# design.net
KiCad netlist of a schematic drawn in EasyEDA Pro
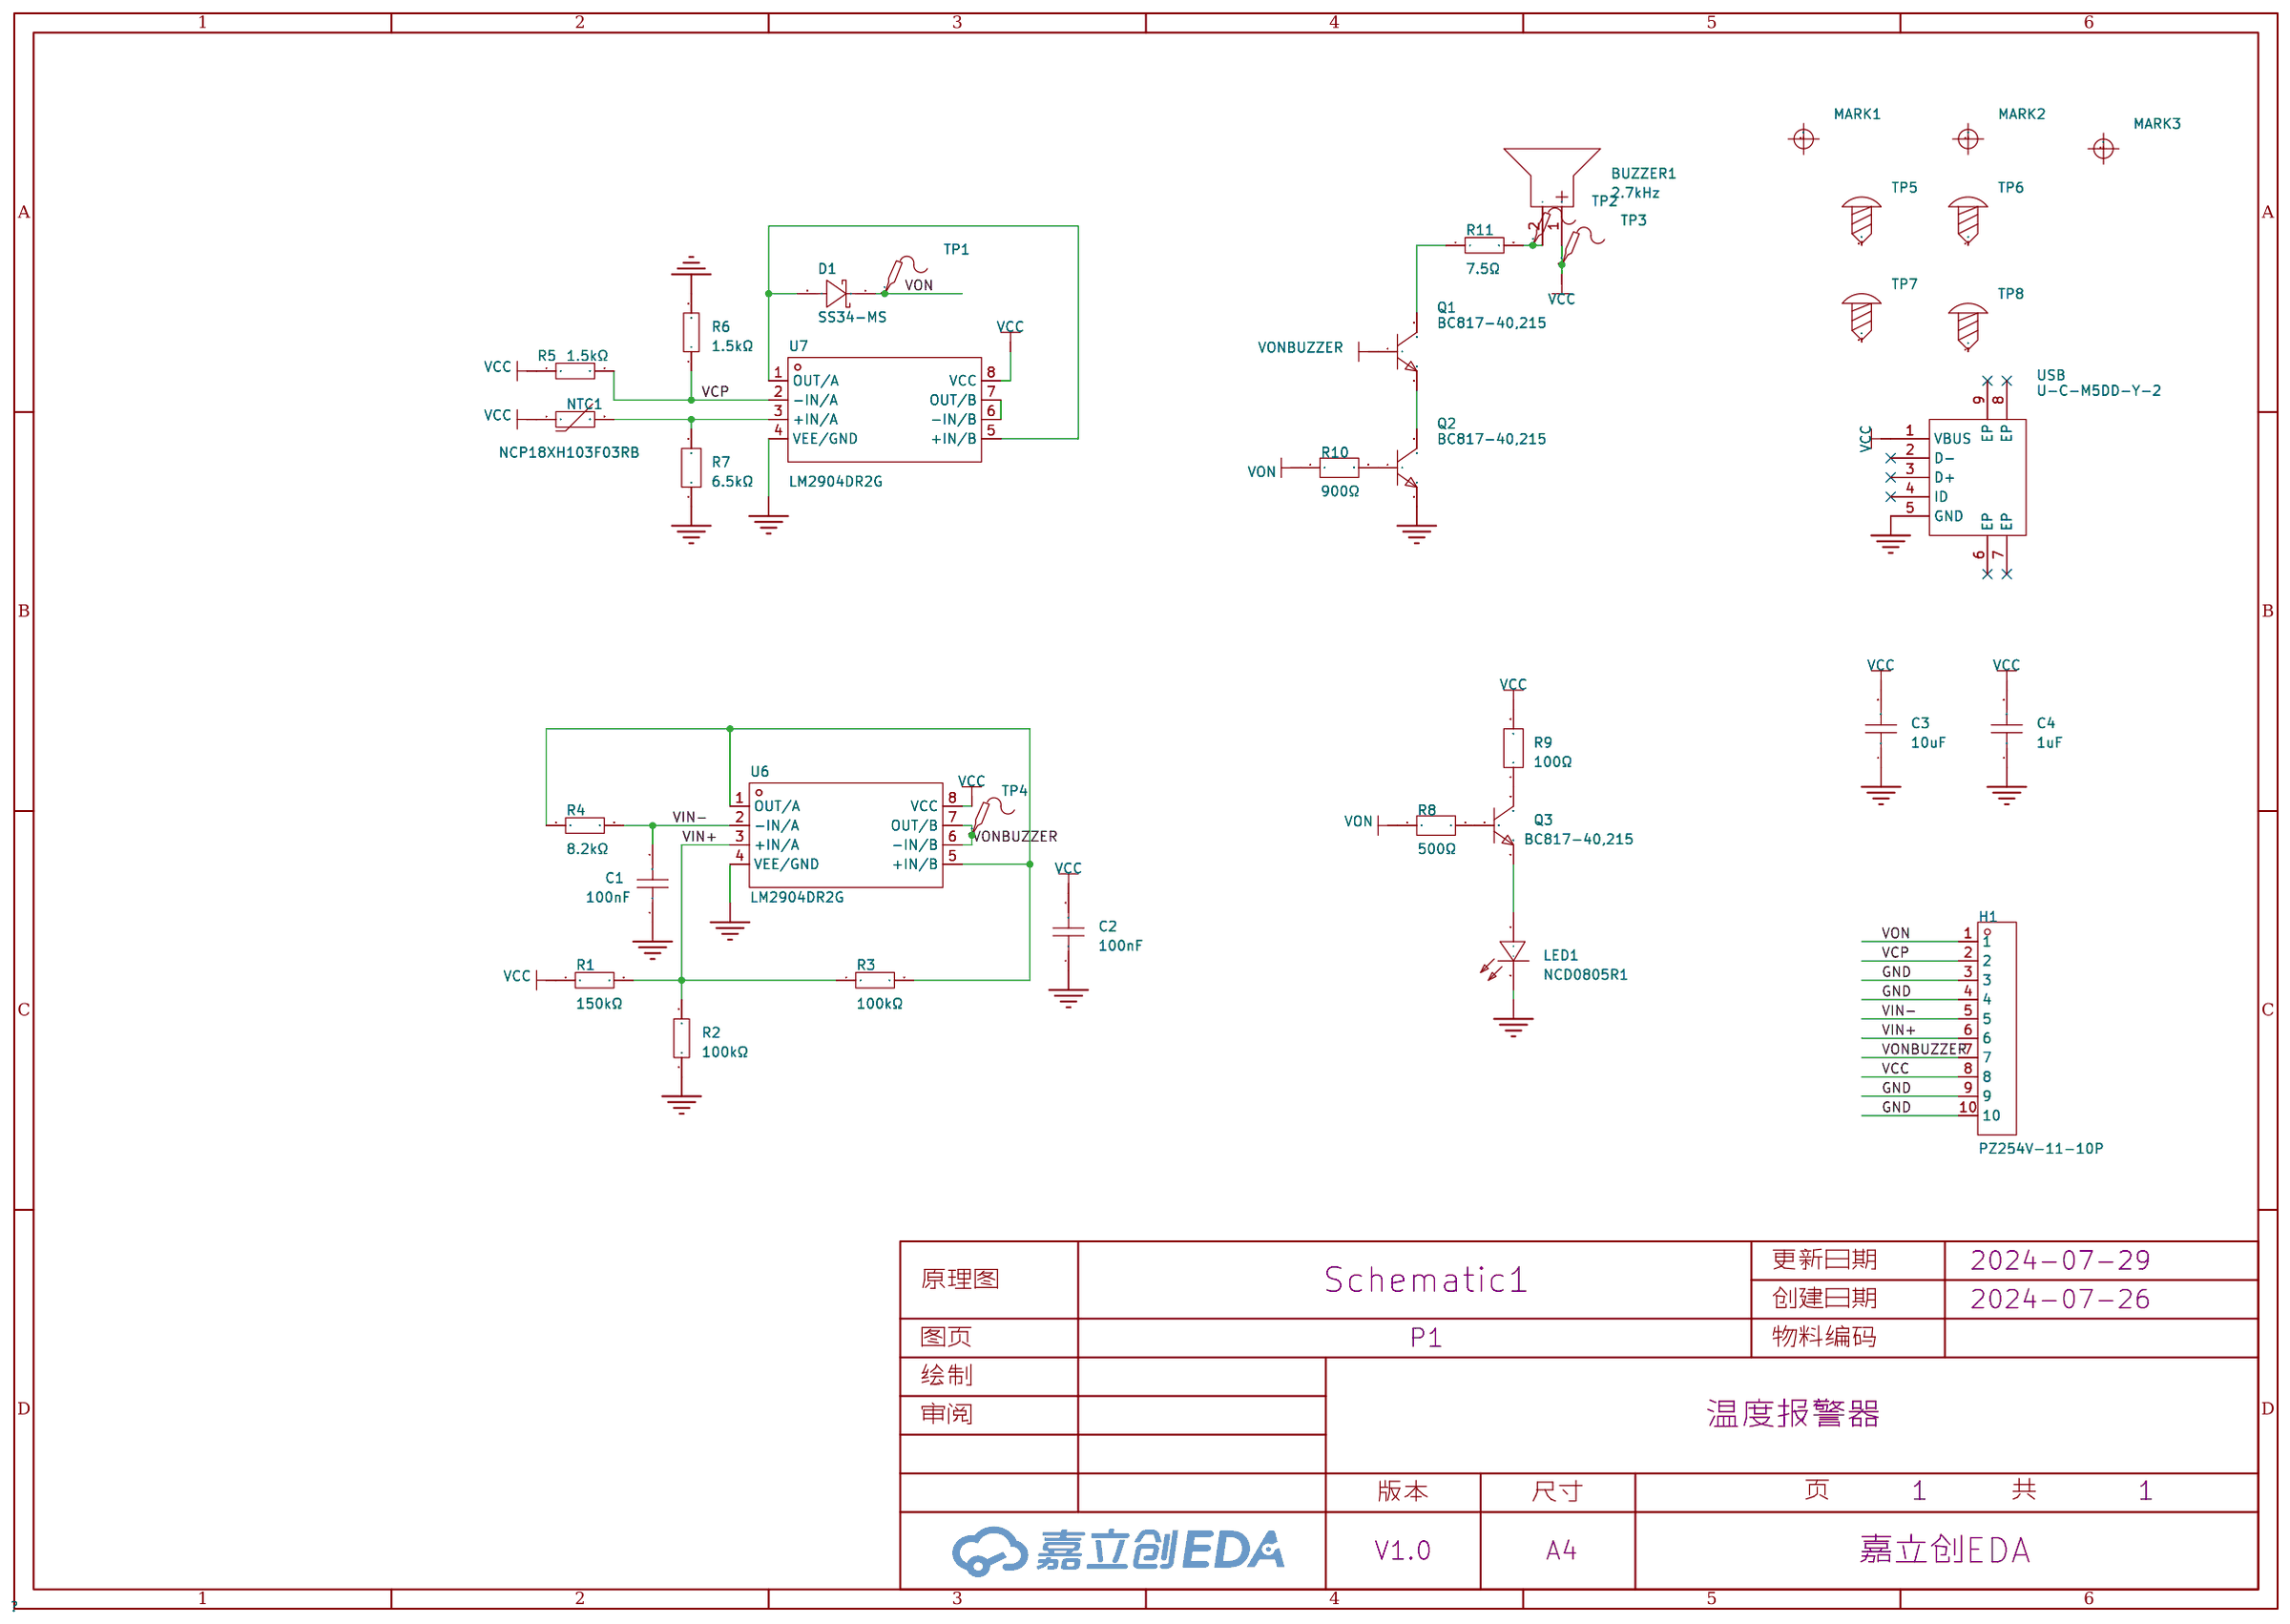
[diagram p0: schematic sheet]

(export (version "E")
  (design (tool "Eeschema 10.0.6"))
  (components
    (comp (ref "BUZZER1")
      (value "2.7kHz")
      (footprint "easyedapro:BUZ-TH_BD9.0-P4.00-D0.6-FD")
      (description "驱动方式:无源(外部驱动);构造类型:电磁式;频率:2.7kHz;声压(SPL):85dB@5V,10cm;")
      (fields
        (field (name "Manufacturer Part") "YS-MBZ9042C05R42")
        (field (name "Manufacturer") "Fengming(锋鸣电子)")
      )
      (libsource (lib "easyedapro") (part "YS-MBZ9042C05R42"))
    )
    (comp (ref "C1")
      (value "100nF")
      (footprint "easyedapro:C0603")
      (description "容值:100nF;精度:±10%;额定电压:50V;材质(温度系数):X7R;")
      (fields
        (field (name "Manufacturer Part") "CC0603KRX7R9BB104")
        (field (name "Manufacturer") "YAGEO(国巨)")
      )
      (libsource (lib "easyedapro") (part "CC0603KRX7R9BB104"))
    )
    (comp (ref "C2")
      (value "100nF")
      (footprint "easyedapro:C0603")
      (description "容值:100nF;精度:±10%;额定电压:50V;材质(温度系数):X7R;")
      (fields
        (field (name "Manufacturer Part") "CC0603KRX7R9BB104")
        (field (name "Manufacturer") "YAGEO(国巨)")
      )
      (libsource (lib "easyedapro") (part "CC0603KRX7R9BB104"))
    )
    (comp (ref "C3")
      (value "10uF")
      (footprint "easyedapro:C0603")
      (description "容值:10uF;精度:±10%;额定电压:10V;材质(温度系数):X5R;")
      (fields
        (field (name "Manufacturer Part") "CL10A106KP8NNNC")
        (field (name "Manufacturer") "SAMSUNG(三星)")
      )
      (libsource (lib "easyedapro") (part "CL10A106KP8NNNC"))
    )
    (comp (ref "C4")
      (value "1uF")
      (footprint "easyedapro:C0603")
      (description "容值:1uF;精度:±10%;额定电压:50V;材质(温度系数):X5R;")
      (fields
        (field (name "Manufacturer Part") "CL10A105KB8NNNC")
        (field (name "Manufacturer") "SAMSUNG(三星)")
      )
      (libsource (lib "easyedapro") (part "CL10A105KB8NNNC"))
    )
    (comp (ref "D1")
      (value "SS34-MS")
      (footprint "easyedapro:DO-214AC_L4.3-W2.7-LS5.0-RD")
      (description "二极管配置:-;正向压降(Vf):550mV@3A;直流反向耐压(Vr):40V;整流电流:3A;")
      (fields (field (name "Manufacturer") "MSKSEMI(美森科)"))
      (libsource (lib "easyedapro") (part "SS34-MS"))
    )
    (comp (ref "H1")
      (value "PZ254V-11-10P")
      (footprint "easyedapro:HDR-TH_10P-P2.54-V-M")
      (fields (field (name "Manufacturer") "XFCN(兴飞)"))
      (libsource (lib "easyedapro") (part "PZ254V-11-10P"))
    )
    (comp (ref "LED1")
      (value "NCD0805R1")
      (footprint "easyedapro:LED0805-R-RD")
      (fields (field (name "Manufacturer") "国星光电"))
      (libsource (lib "easyedapro") (part "FC-2012HRK-620D"))
    )
    (comp (ref "MARK1")
      (value "~")
      (footprint "easyedapro:Mark-Point-1mm")
      (description "Mark点")
      (libsource (lib "easyedapro") (part "Mark-Point"))
    )
    (comp (ref "MARK2")
      (value "~")
      (footprint "easyedapro:Mark-Point-1mm")
      (description "Mark点")
      (libsource (lib "easyedapro") (part "Mark-Point"))
    )
    (comp (ref "MARK3")
      (value "~")
      (footprint "easyedapro:Mark-Point-1mm")
      (description "Mark点")
      (libsource (lib "easyedapro") (part "Mark-Point"))
    )
    (comp (ref "NTC1")
      (value "NCP18XH103F03RB")
      (footprint "easyedapro:R0603")
      (description "阻值(25°C):10kΩ;B值(25°C/50°C):3380K;电阻精度:±1%;功率:100mW;B值精度:±1%;最大稳态电流(25°C):310uA;")
      (fields (field (name "Manufacturer") "muRata(村田)"))
      (libsource (lib "easyedapro") (part "NCP18XH103F03RB"))
    )
    (comp (ref "Q1")
      (value "BC817-40,215")
      (footprint "easyedapro:SOT-23-3_L2.9-W1.6-P1.90-LS2.8-BR")
      (description "晶体管类型:NPN;集电极电流(Ic):500mA;集射极击穿电压(Vceo):45V;功率(Pd):250mW;直流电流增益(hFE@Ic,Vce):250@100mA,1V;")
      (fields (field (name "Manufacturer") "Nexperia(安世)"))
      (libsource (lib "easyedapro") (part "BC817-40,215"))
    )
    (comp (ref "Q2")
      (value "BC817-40,215")
      (footprint "easyedapro:SOT-23-3_L2.9-W1.6-P1.90-LS2.8-BR")
      (description "晶体管类型:NPN;集电极电流(Ic):500mA;集射极击穿电压(Vceo):45V;功率(Pd):250mW;直流电流增益(hFE@Ic,Vce):250@100mA,1V;")
      (fields (field (name "Manufacturer") "Nexperia(安世)"))
      (libsource (lib "easyedapro") (part "BC817-40,215"))
    )
    (comp (ref "Q3")
      (value "BC817-40,215")
      (footprint "easyedapro:SOT-23-3_L2.9-W1.6-P1.90-LS2.8-BR")
      (description "晶体管类型:NPN;集电极电流(Ic):500mA;集射极击穿电压(Vceo):45V;功率(Pd):250mW;直流电流增益(hFE@Ic,Vce):250@100mA,1V;")
      (fields (field (name "Manufacturer") "Nexperia(安世)"))
      (libsource (lib "easyedapro") (part "BC817-40,215"))
    )
    (comp (ref "R1")
      (value "150kΩ")
      (footprint "easyedapro:R0603")
      (description "电阻类型:厚膜电阻;阻值:150kΩ;精度:±1%;功率:100mW;最大工作电压:75V;温度系数:±100ppm/°C;")
      (fields
        (field (name "Manufacturer Part") "0603WAF1503T5E")
        (field (name "Manufacturer") "UNI-ROYAL(厚声)")
      )
      (libsource (lib "easyedapro") (part "0603WAF1503T5E"))
    )
    (comp (ref "R2")
      (value "100kΩ")
      (footprint "easyedapro:R0603")
      (description "电阻类型:厚膜电阻;阻值:100kΩ;精度:±1%;功率:100mW;最大工作电压:75V;温度系数:±100ppm/°C;")
      (fields
        (field (name "Manufacturer Part") "0603WAF1003T5E")
        (field (name "Manufacturer") "UNI-ROYAL(厚声)")
      )
      (libsource (lib "easyedapro") (part "0603WAF1003T5E"))
    )
    (comp (ref "R3")
      (value "100kΩ")
      (footprint "easyedapro:R0603")
      (description "电阻类型:厚膜电阻;阻值:100kΩ;精度:±1%;功率:100mW;最大工作电压:75V;温度系数:±100ppm/°C;")
      (fields
        (field (name "Manufacturer Part") "0603WAF1003T5E")
        (field (name "Manufacturer") "UNI-ROYAL(厚声)")
      )
      (libsource (lib "easyedapro") (part "0603WAF1003T5E"))
    )
    (comp (ref "R4")
      (value "8.2kΩ")
      (footprint "easyedapro:R0603")
      (description "电阻类型:厚膜电阻;阻值:8.2kΩ;精度:±1%;功率:100mW;最大工作电压:75V;温度系数:±100ppm/°C;")
      (fields
        (field (name "Manufacturer Part") "0603WAF8201T5E")
        (field (name "Manufacturer") "UNI-ROYAL(厚声)")
      )
      (libsource (lib "easyedapro") (part "0603WAF8201T5E"))
    )
    (comp (ref "R5")
      (value "1.5kΩ")
      (footprint "easyedapro:R0603")
      (description "电阻类型:厚膜电阻;阻值:1.5kΩ;精度:±1%;功率:100mW;最大工作电压:75V;温度系数:±100ppm/°C;")
      (fields
        (field (name "Manufacturer Part") "0603WAF1501T5E")
        (field (name "Manufacturer") "UNI-ROYAL(厚声)")
      )
      (libsource (lib "easyedapro") (part "0603WAF1501T5E"))
    )
    (comp (ref "R6")
      (value "1.5kΩ")
      (footprint "easyedapro:R0603")
      (description "电阻类型:厚膜电阻;阻值:1.5kΩ;精度:±1%;功率:100mW;最大工作电压:75V;温度系数:±100ppm/°C;")
      (fields
        (field (name "Manufacturer Part") "0603WAF1501T5E")
        (field (name "Manufacturer") "UNI-ROYAL(厚声)")
      )
      (libsource (lib "easyedapro") (part "0603WAF1501T5E"))
    )
    (comp (ref "R7")
      (value "6.5kΩ")
      (footprint "easyedapro:R0603")
      (description "电阻类型:薄膜电阻;阻值:6.5kΩ;精度:±0.1%;功率:100mW;最大工作电压:75V;温度系数:±25ppm/°C;")
      (fields
        (field (name "Manufacturer Part") "MCT06030D6501BP100")
        (field (name "Manufacturer") "VISHAY(威世)")
      )
      (libsource (lib "easyedapro") (part "MCT06030D6501BP100"))
    )
    (comp (ref "R8")
      (value "500Ω")
      (footprint "easyedapro:R0603")
      (description "电阻类型:薄膜电阻;阻值:500Ω;精度:±0.1%;功率:100mW;温度系数:±15ppm/°C;")
      (fields (field (name "Manufacturer Part") "RT0603BRC07500RL") (field (name "Manufacturer") "YAGEO(国巨)"))
      (libsource (lib "easyedapro") (part "RT0603BRC07500RL"))
    )
    (comp (ref "R9")
      (value "100Ω")
      (footprint "easyedapro:R0805")
      (description "电阻类型:厚膜电阻;阻值:100Ω;精度:±5%;功率:400mW;最大工作电压:150V;温度系数:±200ppm/°C;")
      (fields (field (name "Manufacturer Part") "ESR10EZPJ101") (field (name "Manufacturer") "ROHM(罗姆)"))
      (libsource (lib "easyedapro") (part "ESR10EZPJ101"))
    )
    (comp (ref "R10")
      (value "900Ω")
      (footprint "easyedapro:R0603")
      (description "电阻类型:厚膜电阻;阻值:900Ω;精度:±1%;功率:100mW;最大工作电压:75V;")
      (fields (field (name "Manufacturer Part") "SCR0603F900R") (field (name "Manufacturer") "VO(翔胜)"))
      (libsource (lib "easyedapro") (part "SCR0603F900R"))
    )
    (comp (ref "R11")
      (value "7.5Ω")
      (footprint "easyedapro:R1210")
      (description "电阻类型:厚膜电阻;阻值:7.5Ω;精度:±1%;功率:500mW;最大工作电压:200V;温度系数:±200ppm/°C;")
      (fields
        (field (name "Manufacturer Part") "1210W2F750KT5E")
        (field (name "Manufacturer") "UNI-ROYAL(厚声)")
      )
      (libsource (lib "easyedapro") (part "1210W3F750KT5E"))
    )
    (comp (ref "TP1")
      (value "~")
      (footprint "easyedapro:Test-Point-0.5mm")
      (description "Test Point 测试点")
      (libsource (lib "easyedapro") (part "Test-Point"))
    )
    (comp (ref "TP2")
      (value "~")
      (footprint "easyedapro:Test-Point-0.5mm")
      (description "Test Point 测试点")
      (libsource (lib "easyedapro") (part "Test-Point"))
    )
    (comp (ref "TP3")
      (value "~")
      (footprint "easyedapro:Test-Point-0.5mm")
      (description "Test Point 测试点")
      (libsource (lib "easyedapro") (part "Test-Point"))
    )
    (comp (ref "TP4")
      (value "~")
      (footprint "easyedapro:Test-Point-0.5mm")
      (description "Test Point 测试点")
      (libsource (lib "easyedapro") (part "Test-Point"))
    )
    (comp (ref "TP5") (value "~") (footprint "easyedapro:M3螺丝") (libsource (lib "easyedapro") (part "螺丝孔")))
    (comp (ref "TP6") (value "~") (footprint "easyedapro:M3螺丝") (libsource (lib "easyedapro") (part "螺丝孔")))
    (comp (ref "TP7") (value "~") (footprint "easyedapro:M3螺丝") (libsource (lib "easyedapro") (part "螺丝孔")))
    (comp (ref "TP8") (value "~") (footprint "easyedapro:M3螺丝") (libsource (lib "easyedapro") (part "螺丝孔")))
    (comp (ref "U6")
      (value "LM2904DR2G")
      (footprint "easyedapro:SOIC-8_L4.9-W3.9-P1.27-LS6.0-BL")
      (description "放大器数:双路;增益带宽积(GBP):1MHz;输入偏置电流(Ib):45nA;压摆率(SR):-;带宽(-3db):-;")
      (fields (field (name "Manufacturer") "onsemi(安森美)"))
      (libsource (lib "easyedapro") (part "LM2904DR2G"))
    )
    (comp (ref "U7")
      (value "LM2904DR2G")
      (footprint "easyedapro:SOIC-8_L4.9-W3.9-P1.27-LS6.0-BL")
      (description "放大器数:双路;增益带宽积(GBP):1MHz;输入偏置电流(Ib):45nA;压摆率(SR):-;带宽(-3db):-;")
      (fields (field (name "Manufacturer") "onsemi(安森美)"))
      (libsource (lib "easyedapro") (part "LM2904DR2G"))
    )
    (comp (ref "USB")
      (value "U-C-M5DD-Y-2")
      (footprint "easyedapro:MICRO-USB-SMD_U-C-M5DD-Y-2")
      (description "连接器类型:Micro-B;标准:USB 2.0;公母:母;端口数量:1;触点数量:5P;安装方式:沉板;额定电流 - 电源:1A;工作温度范围:-;")
      (fields (field (name "Manufacturer") "韩国韩荣"))
      (libsource (lib "easyedapro") (part "U-C-M5DD-Y-2"))
    )
  )
  (nets
    (net (code "1") (name "/VCP") (class "Default")
      (node (ref "H1") (pin "2") (pinfunction "2_2") (pintype "unspecified"))
      (node (ref "R5") (pin "2") (pinfunction "2_2") (pintype "input"))
      (node (ref "R6") (pin "1") (pinfunction "1_1") (pintype "input"))
      (node (ref "U7") (pin "2") (pinfunction "-IN/A_2") (pintype "unspecified"))
    )
    (net (code "2") (name "/VIN+") (class "Default")
      (node (ref "H1") (pin "6") (pinfunction "6_6") (pintype "unspecified"))
      (node (ref "R1") (pin "2") (pinfunction "2_2") (pintype "input"))
      (node (ref "R2") (pin "2") (pinfunction "2_2") (pintype "input"))
      (node (ref "R3") (pin "1") (pinfunction "1_1") (pintype "input"))
      (node (ref "U6") (pin "3") (pinfunction "+IN/A_3") (pintype "unspecified"))
    )
    (net (code "3") (name "/VIN-") (class "Default")
      (node (ref "C1") (pin "2") (pinfunction "2_2") (pintype "unspecified"))
      (node (ref "H1") (pin "5") (pinfunction "5_5") (pintype "unspecified"))
      (node (ref "R4") (pin "2") (pinfunction "2_2") (pintype "input"))
      (node (ref "U6") (pin "2") (pinfunction "-IN/A_2") (pintype "unspecified"))
    )
    (net (code "4") (name "GND") (class "Default")
      (node (ref "C1") (pin "1") (pinfunction "1_1") (pintype "unspecified"))
      (node (ref "C2") (pin "1") (pinfunction "1_1") (pintype "unspecified"))
      (node (ref "C3") (pin "1") (pinfunction "1_1") (pintype "unspecified"))
      (node (ref "C4") (pin "1") (pinfunction "1_1") (pintype "unspecified"))
      (node (ref "H1") (pin "10") (pinfunction "10_10") (pintype "unspecified"))
      (node (ref "H1") (pin "3") (pinfunction "3_3") (pintype "unspecified"))
      (node (ref "H1") (pin "4") (pinfunction "4_4") (pintype "unspecified"))
      (node (ref "H1") (pin "9") (pinfunction "9_9") (pintype "unspecified"))
      (node (ref "LED1") (pin "2") (pinfunction "-_2") (pintype "unspecified"))
      (node (ref "Q2") (pin "2") (pinfunction "2_2") (pintype "input"))
      (node (ref "R2") (pin "1") (pinfunction "1_1") (pintype "input"))
      (node (ref "R6") (pin "2") (pinfunction "2_2") (pintype "input"))
      (node (ref "R7") (pin "1") (pinfunction "1_1") (pintype "unspecified"))
      (node (ref "U6") (pin "4") (pinfunction "VEE/GND_4") (pintype "unspecified"))
      (node (ref "U7") (pin "4") (pinfunction "VEE/GND_4") (pintype "unspecified"))
      (node (ref "USB") (pin "5") (pinfunction "GND_5") (pintype "unspecified"))
    )
    (net (code "5") (name "Net-(BUZZER1--)") (class "Default")
      (node (ref "BUZZER1") (pin "2") (pinfunction "-_2") (pintype "unspecified"))
      (node (ref "R11") (pin "2") (pinfunction "2_2") (pintype "input"))
      (node (ref "TP2") (pin "1") (pinfunction "1_1") (pintype "input"))
    )
    (net (code "6") (name "Net-(D1-K)") (class "Default")
      (node (ref "D1") (pin "2") (pinfunction "K_2") (pintype "unspecified"))
      (node (ref "U7") (pin "1") (pinfunction "OUT/A_1") (pintype "unspecified"))
      (node (ref "U7") (pin "5") (pinfunction "+IN/B_5") (pintype "unspecified"))
    )
    (net (code "7") (name "Net-(LED1-+)") (class "Default")
      (node (ref "LED1") (pin "1") (pinfunction "+_1") (pintype "unspecified"))
      (node (ref "Q3") (pin "2") (pinfunction "2_2") (pintype "input"))
    )
    (net (code "8") (name "Net-(Q1-Pad2)") (class "Default")
      (node (ref "Q1") (pin "2") (pinfunction "2_2") (pintype "input"))
      (node (ref "Q2") (pin "3") (pinfunction "3_3") (pintype "input"))
    )
    (net (code "9") (name "Net-(Q1-Pad3)") (class "Default")
      (node (ref "Q1") (pin "3") (pinfunction "3_3") (pintype "input"))
      (node (ref "R11") (pin "1") (pinfunction "1_1") (pintype "input"))
    )
    (net (code "10") (name "Net-(Q2-Pad1)") (class "Default")
      (node (ref "Q2") (pin "1") (pinfunction "1_1") (pintype "input"))
      (node (ref "R10") (pin "2") (pinfunction "2_2") (pintype "unspecified"))
    )
    (net (code "11") (name "Net-(Q3-Pad1)") (class "Default")
      (node (ref "Q3") (pin "1") (pinfunction "1_1") (pintype "input"))
      (node (ref "R8") (pin "2") (pinfunction "2_2") (pintype "unspecified"))
    )
    (net (code "12") (name "Net-(Q3-Pad3)") (class "Default")
      (node (ref "Q3") (pin "3") (pinfunction "3_3") (pintype "input"))
      (node (ref "R9") (pin "1") (pinfunction "1_1") (pintype "input"))
    )
    (net (code "13") (name "Net-(U6-+IN{slash}B)") (class "Default")
      (node (ref "R3") (pin "2") (pinfunction "2_2") (pintype "input"))
      (node (ref "R4") (pin "1") (pinfunction "1_1") (pintype "input"))
      (node (ref "U6") (pin "1") (pinfunction "OUT/A_1") (pintype "unspecified"))
      (node (ref "U6") (pin "5") (pinfunction "+IN/B_5") (pintype "unspecified"))
    )
    (net (code "14") (name "Net-(U7-+IN{slash}A)") (class "Default")
      (node (ref "NTC1") (pin "2") (pinfunction "2_2") (pintype "input"))
      (node (ref "R7") (pin "2") (pinfunction "2_2") (pintype "unspecified"))
      (node (ref "U7") (pin "3") (pinfunction "+IN/A_3") (pintype "unspecified"))
    )
    (net (code "15") (name "Net-(U7--IN{slash}B)") (class "Default")
      (node (ref "U7") (pin "6") (pinfunction "-IN/B_6") (pintype "unspecified"))
      (node (ref "U7") (pin "7") (pinfunction "OUT/B_7") (pintype "unspecified"))
    )
    (net (code "16") (name "VCC") (class "Default")
      (node (ref "BUZZER1") (pin "1") (pinfunction "+_1") (pintype "unspecified"))
      (node (ref "C2") (pin "2") (pinfunction "2_2") (pintype "unspecified"))
      (node (ref "C3") (pin "2") (pinfunction "2_2") (pintype "unspecified"))
      (node (ref "C4") (pin "2") (pinfunction "2_2") (pintype "unspecified"))
      (node (ref "H1") (pin "8") (pinfunction "8_8") (pintype "unspecified"))
      (node (ref "NTC1") (pin "1") (pinfunction "1_1") (pintype "input"))
      (node (ref "R1") (pin "1") (pinfunction "1_1") (pintype "input"))
      (node (ref "R5") (pin "1") (pinfunction "1_1") (pintype "input"))
      (node (ref "R9") (pin "2") (pinfunction "2_2") (pintype "input"))
      (node (ref "TP3") (pin "1") (pinfunction "1_1") (pintype "input"))
      (node (ref "U6") (pin "8") (pinfunction "VCC_8") (pintype "unspecified"))
      (node (ref "U7") (pin "8") (pinfunction "VCC_8") (pintype "unspecified"))
      (node (ref "USB") (pin "1") (pinfunction "VBUS_1") (pintype "unspecified"))
    )
    (net (code "17") (name "VON") (class "Default")
      (node (ref "D1") (pin "1") (pinfunction "A_1") (pintype "unspecified"))
      (node (ref "H1") (pin "1") (pinfunction "1_1") (pintype "unspecified"))
      (node (ref "R10") (pin "1") (pinfunction "1_1") (pintype "unspecified"))
      (node (ref "R8") (pin "1") (pinfunction "1_1") (pintype "unspecified"))
      (node (ref "TP1") (pin "1") (pinfunction "1_1") (pintype "input"))
    )
    (net (code "18") (name "VONBUZZER") (class "Default")
      (node (ref "H1") (pin "7") (pinfunction "7_7") (pintype "unspecified"))
      (node (ref "Q1") (pin "1") (pinfunction "1_1") (pintype "input"))
      (node (ref "TP4") (pin "1") (pinfunction "1_1") (pintype "input"))
      (node (ref "U6") (pin "6") (pinfunction "-IN/B_6") (pintype "unspecified"))
      (node (ref "U6") (pin "7") (pinfunction "OUT/B_7") (pintype "unspecified"))
    )
    (net (code "19") (name "unconnected-(MARK1-Pad1)") (class "Default")
      (node (ref "MARK1") (pin "1") (pinfunction "1_1") (pintype "input"))
    )
    (net (code "20") (name "unconnected-(MARK2-Pad1)") (class "Default")
      (node (ref "MARK2") (pin "1") (pinfunction "1_1") (pintype "input"))
    )
    (net (code "21") (name "unconnected-(MARK3-Pad1)") (class "Default")
      (node (ref "MARK3") (pin "1") (pinfunction "1_1") (pintype "input"))
    )
    (net (code "22") (name "unconnected-(TP5-Pad1)") (class "Default")
      (node (ref "TP5") (pin "1") (pinfunction "1_1") (pintype "input"))
    )
    (net (code "23") (name "unconnected-(TP6-Pad1)") (class "Default")
      (node (ref "TP6") (pin "1") (pinfunction "1_1") (pintype "input"))
    )
    (net (code "24") (name "unconnected-(TP7-Pad1)") (class "Default")
      (node (ref "TP7") (pin "1") (pinfunction "1_1") (pintype "input"))
    )
    (net (code "25") (name "unconnected-(TP8-Pad1)") (class "Default")
      (node (ref "TP8") (pin "1") (pinfunction "1_1") (pintype "input"))
    )
    (net (code "26") (name "unconnected-(USB-D+-Pad3)") (class "Default")
      (node (ref "USB") (pin "3") (pinfunction "D+_3") (pintype "unspecified+no_connect"))
    )
    (net (code "27") (name "unconnected-(USB-D--Pad2)") (class "Default")
      (node (ref "USB") (pin "2") (pinfunction "D-_2") (pintype "unspecified+no_connect"))
    )
    (net (code "28") (name "unconnected-(USB-EP-Pad6)") (class "Default")
      (node (ref "USB") (pin "6") (pinfunction "EP_6") (pintype "unspecified+no_connect"))
    )
    (net (code "29") (name "unconnected-(USB-EP-Pad7)") (class "Default")
      (node (ref "USB") (pin "7") (pinfunction "EP_7") (pintype "unspecified+no_connect"))
    )
    (net (code "30") (name "unconnected-(USB-EP-Pad8)") (class "Default")
      (node (ref "USB") (pin "8") (pinfunction "EP_8") (pintype "unspecified+no_connect"))
    )
    (net (code "31") (name "unconnected-(USB-EP-Pad9)") (class "Default")
      (node (ref "USB") (pin "9") (pinfunction "EP_9") (pintype "unspecified+no_connect"))
    )
    (net (code "32") (name "unconnected-(USB-ID-Pad4)") (class "Default")
      (node (ref "USB") (pin "4") (pinfunction "ID_4") (pintype "unspecified+no_connect"))
    )
  )
)
